# FreqDiv.net
KiCad netlist of a schematic drawn in Altium Designer
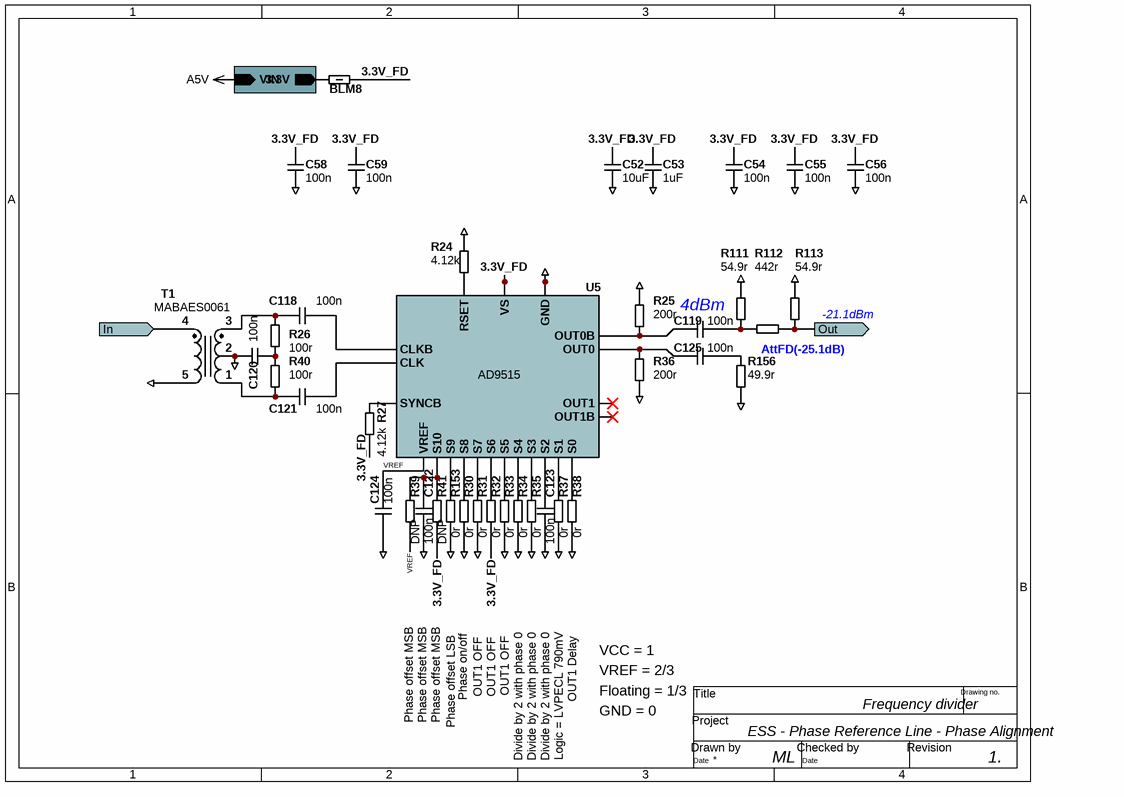
[diagram p0: FreqDiv.SchDoc]

(export (version "E")
  (design (tool "Eeschema 10.0.6"))
  (components
    (comp (ref "BLM8")
      (value "120 Ohms @ 100MHz")
      (footprint "0402-Inductor")
      (description "120 Ohms @ 100MHz 1 Power, Signal Line Ferrite Bead 0402 (1005 Metric) 700mA 130mOhm")
      (libsource (lib "PRL_PDC") (part "BLM15AX121SZ1D"))
    )
    (comp (ref "C52")
      (value "10uF")
      (footprint "1206-capacitor")
      (description "Capacitor 1206")
      (fields (field (name "TOLERANCE") "±20%"))
      (libsource (lib "PRL_PDC") (part "C_1206"))
    )
    (comp (ref "C53")
      (value "1uF")
      (footprint "0603-Capacitor")
      (description "Capacitor 0603")
      (fields (field (name "TOLERANCE") "±20%"))
      (libsource (lib "PRL_PDC") (part "C_0603"))
    )
    (comp (ref "C54")
      (value "100n")
      (footprint "0402-Capacitor")
      (description "Capacitor 0402")
      (fields (field (name "TOLERANCE") "±20%"))
      (libsource (lib "PRL_PDC") (part "C_0402"))
    )
    (comp (ref "C55")
      (value "100n")
      (footprint "0402-Capacitor")
      (description "Capacitor 0402")
      (fields (field (name "TOLERANCE") "±20%"))
      (libsource (lib "PRL_PDC") (part "C_0402"))
    )
    (comp (ref "C56")
      (value "100n")
      (footprint "0402-Capacitor")
      (description "Capacitor 0402")
      (fields (field (name "TOLERANCE") "±20%"))
      (libsource (lib "PRL_PDC") (part "C_0402"))
    )
    (comp (ref "C58")
      (value "100n")
      (footprint "0402-Capacitor")
      (description "Capacitor 0402")
      (fields (field (name "TOLERANCE") "±20%"))
      (libsource (lib "PRL_PDC") (part "C_0402"))
    )
    (comp (ref "C59")
      (value "100n")
      (footprint "0402-Capacitor")
      (description "Capacitor 0402")
      (fields (field (name "TOLERANCE") "±20%"))
      (libsource (lib "PRL_PDC") (part "C_0402"))
    )
    (comp (ref "C118")
      (value "100n")
      (footprint "0402-Capacitor")
      (description "Capacitor 0402")
      (fields (field (name "TOLERANCE") "±20%"))
      (libsource (lib "PRL_PDC") (part "C_0402"))
    )
    (comp (ref "C119")
      (value "100n")
      (footprint "0402-Capacitor")
      (description "Capacitor 0402")
      (fields (field (name "TOLERANCE") "±20%"))
      (libsource (lib "PRL_PDC") (part "C_0402"))
    )
    (comp (ref "C120")
      (value "100n")
      (footprint "0402-Capacitor")
      (description "Capacitor 0402")
      (fields (field (name "TOLERANCE") "±20%"))
      (libsource (lib "PRL_PDC") (part "C_0402"))
    )
    (comp (ref "C121")
      (value "100n")
      (footprint "0402-Capacitor")
      (description "Capacitor 0402")
      (fields (field (name "TOLERANCE") "±20%"))
      (libsource (lib "PRL_PDC") (part "C_0402"))
    )
    (comp (ref "C122")
      (value "100n")
      (footprint "0402-Capacitor")
      (description "Capacitor 0402")
      (fields (field (name "TOLERANCE") "±20%"))
      (libsource (lib "PRL_PDC") (part "C_0402"))
    )
    (comp (ref "C123")
      (value "100n")
      (footprint "0402-Capacitor")
      (description "Capacitor 0402")
      (fields (field (name "TOLERANCE") "±20%"))
      (libsource (lib "PRL_PDC") (part "C_0402"))
    )
    (comp (ref "C124")
      (value "100n")
      (footprint "0402-Capacitor")
      (description "Capacitor 0402")
      (fields (field (name "TOLERANCE") "±20%"))
      (libsource (lib "PRL_PDC") (part "C_0402"))
    )
    (comp (ref "C125")
      (value "100n")
      (footprint "0402-Capacitor")
      (description "Capacitor 0402")
      (fields (field (name "TOLERANCE") "±20%"))
      (libsource (lib "PRL_PDC") (part "C_0402"))
    )
    (comp (ref "R24")
      (value "4.12k")
      (footprint "0402-RESISTOR")
      (description "Resistor 0402")
      (fields (field (name "TOLERANCE") "±1%"))
      (libsource (lib "") (part "R_0402_1"))
    )
    (comp (ref "R25")
      (value "200r")
      (footprint "0402-RESISTOR")
      (description "Resistor 0402")
      (fields (field (name "TOLERANCE") "±1%"))
      (libsource (lib "PRL_PDC") (part "R_0402"))
    )
    (comp (ref "R26")
      (value "100r")
      (footprint "0402-RESISTOR")
      (description "Resistor 0402")
      (fields (field (name "TOLERANCE") "±1%"))
      (libsource (lib "PRL_PDC") (part "R_0402"))
    )
    (comp (ref "R27")
      (value "4.12k")
      (footprint "0402-RESISTOR")
      (description "Resistor 0402")
      (fields (field (name "TOLERANCE") "±1%"))
      (libsource (lib "PRL_PDC") (part "R_0402"))
    )
    (comp (ref "R30")
      (value "0r")
      (footprint "0402-RESISTOR")
      (description "Resistor 0402")
      (fields (field (name "TOLERANCE") "±1%"))
      (libsource (lib "PRL_PDC") (part "R_0402"))
    )
    (comp (ref "R31")
      (value "0r")
      (footprint "0402-RESISTOR")
      (description "Resistor 0402")
      (fields (field (name "TOLERANCE") "±1%"))
      (libsource (lib "PRL_PDC") (part "R_0402"))
    )
    (comp (ref "R32")
      (value "0r")
      (footprint "0402-RESISTOR")
      (description "Resistor 0402")
      (fields (field (name "TOLERANCE") "±1%"))
      (libsource (lib "PRL_PDC") (part "R_0402"))
    )
    (comp (ref "R33")
      (value "0r")
      (footprint "0402-RESISTOR")
      (description "Resistor 0402")
      (fields (field (name "TOLERANCE") "±1%"))
      (libsource (lib "PRL_PDC") (part "R_0402"))
    )
    (comp (ref "R34")
      (value "0r")
      (footprint "0402-RESISTOR")
      (description "Resistor 0402")
      (fields (field (name "TOLERANCE") "±1%"))
      (libsource (lib "PRL_PDC") (part "R_0402"))
    )
    (comp (ref "R35")
      (value "0r")
      (footprint "0402-RESISTOR")
      (description "Resistor 0402")
      (fields (field (name "TOLERANCE") "±1%"))
      (libsource (lib "PRL_PDC") (part "R_0402"))
    )
    (comp (ref "R36")
      (value "200r")
      (footprint "0402-RESISTOR")
      (description "Resistor 0402")
      (fields (field (name "TOLERANCE") "±1%"))
      (libsource (lib "PRL_PDC") (part "R_0402"))
    )
    (comp (ref "R37")
      (value "0r")
      (footprint "0402-RESISTOR")
      (description "Resistor 0402")
      (fields (field (name "TOLERANCE") "±1%"))
      (libsource (lib "PRL_PDC") (part "R_0402"))
    )
    (comp (ref "R38")
      (value "0r")
      (footprint "0402-RESISTOR")
      (description "Resistor 0402")
      (fields (field (name "TOLERANCE") "±1%"))
      (libsource (lib "PRL_PDC") (part "R_0402"))
    )
    (comp (ref "R39")
      (value "DNP")
      (footprint "0402-RESISTOR")
      (description "Resistor 0402")
      (fields (field (name "TOLERANCE") "±1%"))
      (libsource (lib "PRL_PDC") (part "R_0402"))
    )
    (comp (ref "R40")
      (value "100r")
      (footprint "0402-RESISTOR")
      (description "Resistor 0402")
      (fields (field (name "TOLERANCE") "±1%"))
      (libsource (lib "PRL_PDC") (part "R_0402"))
    )
    (comp (ref "R41")
      (value "DNP")
      (footprint "0402-RESISTOR")
      (description "Resistor 0402")
      (fields (field (name "TOLERANCE") "±1%"))
      (libsource (lib "PRL_PDC") (part "R_0402"))
    )
    (comp (ref "R111")
      (value "54.9r")
      (footprint "0603-RESISTOR")
      (description "Resistor 0603")
      (fields (field (name "TOLERANCE") "±1%"))
      (libsource (lib "PRL_PDC") (part "R_0603"))
    )
    (comp (ref "R112")
      (value "442r")
      (footprint "0603-RESISTOR")
      (description "Resistor 0603")
      (fields (field (name "TOLERANCE") "±1%"))
      (libsource (lib "") (part "R_0603_1"))
    )
    (comp (ref "R113")
      (value "54.9r")
      (footprint "0603-RESISTOR")
      (description "Resistor 0603")
      (fields (field (name "TOLERANCE") "±1%"))
      (libsource (lib "PRL_PDC") (part "R_0603"))
    )
    (comp (ref "R153")
      (value "0r")
      (footprint "0402-RESISTOR")
      (description "Resistor 0402")
      (fields (field (name "TOLERANCE") "±1%"))
      (libsource (lib "PRL_PDC") (part "R_0402"))
    )
    (comp (ref "R156")
      (value "49.9r")
      (footprint "0402-RESISTOR")
      (description "Resistor 0402")
      (fields (field (name "TOLERANCE") "±1%"))
      (libsource (lib "") (part "R_0402_1"))
    )
    (comp (ref "T1")
      (value "MABAES0061")
      (footprint "MABAES0061")
      (description "1:4 E-Series, RF Flux Coupled Transformer\r\n2 - 800 MHz")
      (libsource (lib "PRL_PDC") (part "MABAES0061"))
    )
    (comp (ref "U5")
      (value "AD9515")
      (footprint "LFCSP-32")
      (description "1.6 GHz Clock Distribution IC, Dividers, Delay Adjust, Two Outputs")
      (libsource (lib "PRL_PDC") (part "AD9515"))
    )
  )
  (nets
    (net (code "1") (name "/3.3V") (class "Default") (node (ref "BLM8") (pin "2") (pintype "passive")))
    (net (code "2") (name "/3.3V_FD") (class "Default")
      (node (ref "BLM8") (pin "1") (pintype "passive"))
      (node (ref "C52") (pin "1") (pinfunction "1_1") (pintype "passive"))
      (node (ref "C53") (pin "1") (pinfunction "1_1") (pintype "passive"))
      (node (ref "C54") (pin "1") (pinfunction "1_1") (pintype "passive"))
      (node (ref "C55") (pin "1") (pinfunction "1_1") (pintype "passive"))
      (node (ref "C56") (pin "1") (pinfunction "1_1") (pintype "passive"))
      (node (ref "C58") (pin "1") (pinfunction "1_1") (pintype "passive"))
      (node (ref "C59") (pin "1") (pinfunction "1_1") (pintype "passive"))
      (node (ref "R27") (pin "2") (pinfunction "2_2") (pintype "passive"))
      (node (ref "R32") (pin "2") (pinfunction "2_2") (pintype "passive"))
      (node (ref "R41") (pin "2") (pinfunction "2_2") (pintype "passive"))
      (node (ref "U5") (pin "1") (pinfunction "VS_1") (pintype "passive"))
      (node (ref "U5") (pin "17") (pinfunction "VS_17") (pintype "passive"))
      (node (ref "U5") (pin "20") (pinfunction "VS_20") (pintype "passive"))
      (node (ref "U5") (pin "21") (pinfunction "VS_21") (pintype "passive"))
      (node (ref "U5") (pin "24") (pinfunction "VS_24") (pintype "passive"))
      (node (ref "U5") (pin "26") (pinfunction "VS_26") (pintype "passive"))
      (node (ref "U5") (pin "29") (pinfunction "VS_29") (pintype "passive"))
      (node (ref "U5") (pin "30") (pinfunction "VS_30") (pintype "passive"))
      (node (ref "U5") (pin "4") (pinfunction "VS_4") (pintype "passive"))
    )
    (net (code "3") (name "/In") (class "Default")
      (node (ref "T1") (pin "4") (pinfunction "4_4") (pintype "passive"))
    )
    (net (code "4") (name "/Out") (class "Default")
      (node (ref "R112") (pin "2") (pinfunction "2_2") (pintype "passive"))
      (node (ref "R113") (pin "2") (pinfunction "2_2") (pintype "passive"))
    )
    (net (code "5") (name "/VREF") (class "Default")
      (node (ref "C124") (pin "1") (pinfunction "1_1") (pintype "passive"))
      (node (ref "R39") (pin "2") (pinfunction "2_2") (pintype "passive"))
      (node (ref "U5") (pin "6") (pinfunction "VREF_6") (pintype "passive"))
    )
    (net (code "7") (name "GND") (class "Default")
      (node (ref "C120") (pin "2") (pinfunction "2_2") (pintype "passive"))
      (node (ref "C122") (pin "2") (pinfunction "2_2") (pintype "passive"))
      (node (ref "C123") (pin "2") (pinfunction "2_2") (pintype "passive"))
      (node (ref "C124") (pin "2") (pinfunction "2_2") (pintype "passive"))
      (node (ref "C52") (pin "2") (pinfunction "2_2") (pintype "passive"))
      (node (ref "C53") (pin "2") (pinfunction "2_2") (pintype "passive"))
      (node (ref "C54") (pin "2") (pinfunction "2_2") (pintype "passive"))
      (node (ref "C55") (pin "2") (pinfunction "2_2") (pintype "passive"))
      (node (ref "C56") (pin "2") (pinfunction "2_2") (pintype "passive"))
      (node (ref "C58") (pin "2") (pinfunction "2_2") (pintype "passive"))
      (node (ref "C59") (pin "2") (pinfunction "2_2") (pintype "passive"))
      (node (ref "R111") (pin "1") (pinfunction "1_1") (pintype "passive"))
      (node (ref "R113") (pin "1") (pinfunction "1_1") (pintype "passive"))
      (node (ref "R153") (pin "2") (pinfunction "2_2") (pintype "passive"))
      (node (ref "R156") (pin "1") (pinfunction "1_1") (pintype "passive"))
      (node (ref "R24") (pin "2") (pinfunction "2_2") (pintype "passive"))
      (node (ref "R25") (pin "1") (pinfunction "1_1") (pintype "passive"))
      (node (ref "R30") (pin "2") (pinfunction "2_2") (pintype "passive"))
      (node (ref "R31") (pin "2") (pinfunction "2_2") (pintype "passive"))
      (node (ref "R33") (pin "2") (pinfunction "2_2") (pintype "passive"))
      (node (ref "R34") (pin "2") (pinfunction "2_2") (pintype "passive"))
      (node (ref "R35") (pin "2") (pinfunction "2_2") (pintype "passive"))
      (node (ref "R36") (pin "2") (pinfunction "2_2") (pintype "passive"))
      (node (ref "R37") (pin "2") (pinfunction "2_2") (pintype "passive"))
      (node (ref "R38") (pin "2") (pinfunction "2_2") (pintype "passive"))
      (node (ref "T1") (pin "2") (pinfunction "2_2") (pintype "passive"))
      (node (ref "T1") (pin "5") (pinfunction "5_5") (pintype "passive"))
      (node (ref "U5") (pin "31") (pinfunction "GND_31") (pintype "passive"))
      (node (ref "U5") (pin "EP") (pinfunction "EP_EP") (pintype "passive"))
    )
    (net (code "8") (name "Net-(C118-Pad2)") (class "Default")
      (node (ref "C118") (pin "2") (pinfunction "2_2") (pintype "passive"))
      (node (ref "R26") (pin "1") (pinfunction "1_1") (pintype "passive"))
      (node (ref "T1") (pin "3") (pinfunction "3_3") (pintype "passive"))
    )
    (net (code "9") (name "Net-(C119-Pad1)") (class "Default")
      (node (ref "C119") (pin "1") (pinfunction "1_1") (pintype "passive"))
      (node (ref "R111") (pin "2") (pinfunction "2_2") (pintype "passive"))
      (node (ref "R112") (pin "1") (pinfunction "1_1") (pintype "passive"))
    )
    (net (code "10") (name "Net-(C120-Pad1)") (class "Default")
      (node (ref "C120") (pin "1") (pinfunction "1_1") (pintype "passive"))
      (node (ref "R26") (pin "2") (pinfunction "2_2") (pintype "passive"))
      (node (ref "R40") (pin "1") (pinfunction "1_1") (pintype "passive"))
    )
    (net (code "11") (name "Net-(C121-Pad2)") (class "Default")
      (node (ref "C121") (pin "2") (pinfunction "2_2") (pintype "passive"))
      (node (ref "R40") (pin "2") (pinfunction "2_2") (pintype "passive"))
      (node (ref "T1") (pin "1") (pinfunction "1_1") (pintype "passive"))
    )
    (net (code "12") (name "Net-(C125-Pad1)") (class "Default")
      (node (ref "C125") (pin "1") (pinfunction "1_1") (pintype "passive"))
      (node (ref "R156") (pin "2") (pinfunction "2_2") (pintype "passive"))
    )
    (net (code "13") (name "Net-(U5-CLK)") (class "Default")
      (node (ref "C121") (pin "1") (pinfunction "1_1") (pintype "passive"))
      (node (ref "U5") (pin "2") (pinfunction "CLK_2") (pintype "passive"))
    )
    (net (code "14") (name "Net-(U5-CLKB)") (class "Default")
      (node (ref "C118") (pin "1") (pinfunction "1_1") (pintype "passive"))
      (node (ref "U5") (pin "3") (pinfunction "CLKB_3") (pintype "passive"))
    )
    (net (code "15") (name "Net-(U5-OUT0)") (class "Default")
      (node (ref "C125") (pin "2") (pinfunction "2_2") (pintype "passive"))
      (node (ref "R36") (pin "1") (pinfunction "1_1") (pintype "passive"))
      (node (ref "U5") (pin "23") (pinfunction "OUT0_23") (pintype "passive"))
    )
    (net (code "16") (name "Net-(U5-OUT0B)") (class "Default")
      (node (ref "C119") (pin "2") (pinfunction "2_2") (pintype "passive"))
      (node (ref "R25") (pin "2") (pinfunction "2_2") (pintype "passive"))
      (node (ref "U5") (pin "22") (pinfunction "OUT0B_22") (pintype "passive"))
    )
    (net (code "17") (name "Net-(U5-RSET)") (class "Default")
      (node (ref "R24") (pin "1") (pinfunction "1_1") (pintype "passive"))
      (node (ref "U5") (pin "32") (pinfunction "RSET_32") (pintype "passive"))
    )
    (net (code "18") (name "Net-(U5-S0)") (class "Default")
      (node (ref "R38") (pin "1") (pinfunction "1_1") (pintype "passive"))
      (node (ref "U5") (pin "25") (pinfunction "S0_25") (pintype "passive"))
    )
    (net (code "19") (name "Net-(U5-S1)") (class "Default")
      (node (ref "R37") (pin "1") (pinfunction "1_1") (pintype "passive"))
      (node (ref "U5") (pin "16") (pinfunction "S1_16") (pintype "passive"))
    )
    (net (code "20") (name "Net-(U5-S2)") (class "Default")
      (node (ref "C123") (pin "1") (pinfunction "1_1") (pintype "passive"))
      (node (ref "U5") (pin "15") (pinfunction "S2_15") (pintype "passive"))
    )
    (net (code "21") (name "Net-(U5-S3)") (class "Default")
      (node (ref "R35") (pin "1") (pinfunction "1_1") (pintype "passive"))
      (node (ref "U5") (pin "14") (pinfunction "S3_14") (pintype "passive"))
    )
    (net (code "22") (name "Net-(U5-S4)") (class "Default")
      (node (ref "R34") (pin "1") (pinfunction "1_1") (pintype "passive"))
      (node (ref "U5") (pin "13") (pinfunction "S4_13") (pintype "passive"))
    )
    (net (code "23") (name "Net-(U5-S5)") (class "Default")
      (node (ref "R33") (pin "1") (pinfunction "1_1") (pintype "passive"))
      (node (ref "U5") (pin "12") (pinfunction "S5_12") (pintype "passive"))
    )
    (net (code "24") (name "Net-(U5-S6)") (class "Default")
      (node (ref "R32") (pin "1") (pinfunction "1_1") (pintype "passive"))
      (node (ref "U5") (pin "11") (pinfunction "S6_11") (pintype "passive"))
    )
    (net (code "25") (name "Net-(U5-S7)") (class "Default")
      (node (ref "R31") (pin "1") (pinfunction "1_1") (pintype "passive"))
      (node (ref "U5") (pin "10") (pinfunction "S7_10") (pintype "passive"))
    )
    (net (code "26") (name "Net-(U5-S8)") (class "Default")
      (node (ref "R30") (pin "1") (pinfunction "1_1") (pintype "passive"))
      (node (ref "U5") (pin "9") (pinfunction "S8_9") (pintype "passive"))
    )
    (net (code "27") (name "Net-(U5-S9)") (class "Default")
      (node (ref "R153") (pin "1") (pinfunction "1_1") (pintype "passive"))
      (node (ref "U5") (pin "8") (pinfunction "S9_8") (pintype "passive"))
    )
    (net (code "28") (name "Net-(U5-S10)") (class "Default")
      (node (ref "C122") (pin "1") (pinfunction "1_1") (pintype "passive"))
      (node (ref "R39") (pin "1") (pinfunction "1_1") (pintype "passive"))
      (node (ref "R41") (pin "1") (pinfunction "1_1") (pintype "passive"))
      (node (ref "U5") (pin "7") (pinfunction "S10_7") (pintype "passive"))
    )
    (net (code "29") (name "Net-(U5-SYNCB)") (class "Default")
      (node (ref "R27") (pin "1") (pinfunction "1_1") (pintype "passive"))
      (node (ref "U5") (pin "5") (pinfunction "SYNCB_5") (pintype "passive"))
    )
    (net (code "30") (name "unconnected-(U5-DNC-Pad27)") (class "Default")
      (node (ref "U5") (pin "27") (pinfunction "DNC_27") (pintype "passive"))
    )
    (net (code "31") (name "unconnected-(U5-DNC-Pad28)") (class "Default")
      (node (ref "U5") (pin "28") (pinfunction "DNC_28") (pintype "passive"))
    )
    (net (code "32") (name "unconnected-(U5-OUT1-Pad19)") (class "Default")
      (node (ref "U5") (pin "19") (pinfunction "OUT1_19") (pintype "passive+no_connect"))
    )
    (net (code "33") (name "unconnected-(U5-OUT1B-Pad18)") (class "Default")
      (node (ref "U5") (pin "18") (pinfunction "OUT1B_18") (pintype "passive+no_connect"))
    )
  )
)
